# schematic_easyeda.net
KiCad netlist of a schematic drawn in EasyEDA
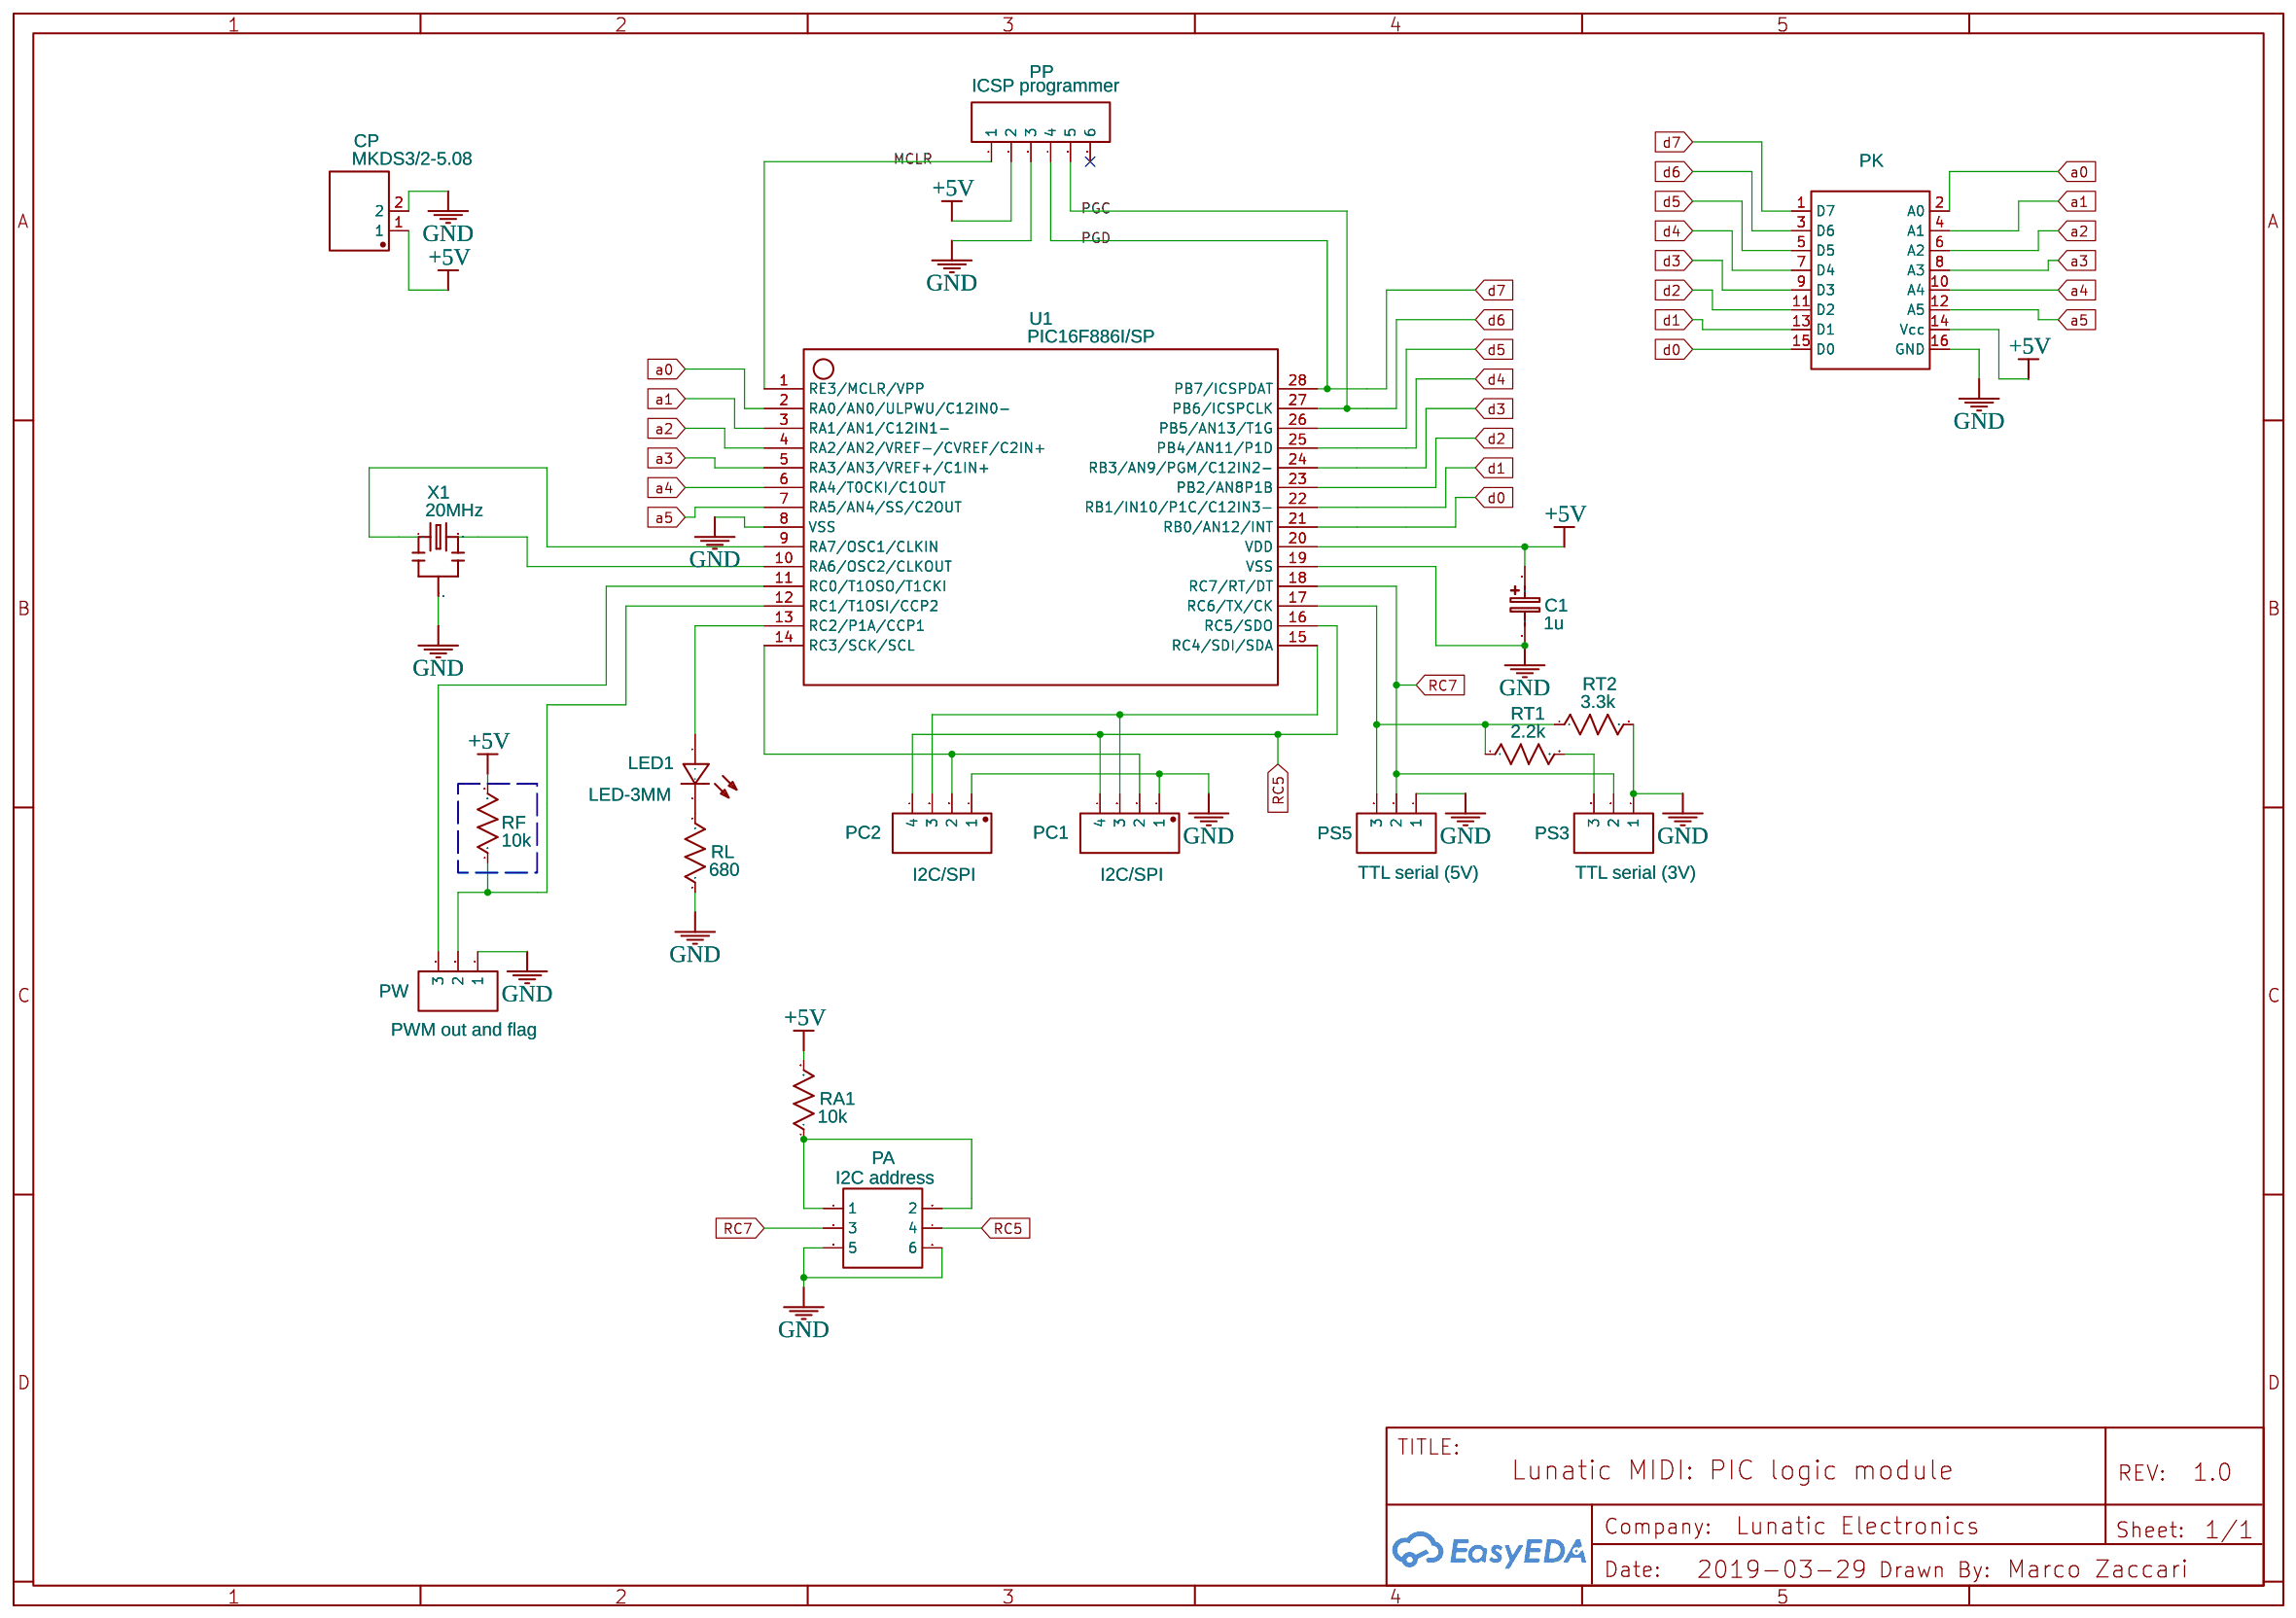
[diagram p0: schematic sheet]

(export (version "E")
  (design (tool "Eeschema 10.0.6"))
  (components
    (comp (ref "C1")
      (value "1u")
      (fields (field (name "BOM_Manufacturer Part") "?"))
      (libsource (lib "") (part "Cap_Electrolytic(TH)_D3.0XF1.5_EU"))
    )
    (comp (ref "CP")
      (value "MKDS3/2-5.08")
      (fields (field (name "BOM_Supplier Part") "C89120"))
      (libsource (lib "") (part "Unknown_180_100"))
    )
    (comp (ref "LED1")
      (value "LED-3MM")
      (fields
        (field (name "BOM_Manufacturer Part") "204-10SURD/S530-A3")
        (field (name "BOM_Supplier Part") "C99772")
      )
      (libsource (lib "") (part "Unknown_345_385"))
    )
    (comp (ref "PA")
      (value "I2C address")
      (fields
        (field (name "BOM_Manufacturer Part") "Header-Male-2.54_2x3")
        (field (name "BOM_Supplier Part") "C65114")
      )
      (libsource (lib "") (part "Unknown_440_615"))
    )
    (comp (ref "PC1")
      (value "I2C/SPI")
      (fields
        (field (name "BOM_Manufacturer Part") "210S-1*4P L=11.6MMGold-plated black")
        (field (name "BOM_Supplier Part") "C124378")
      )
      (libsource (lib "") (part "Unknown_565_410"))
    )
    (comp (ref "PC2")
      (value "I2C/SPI")
      (fields
        (field (name "BOM_Manufacturer Part") "210S-1*4P L=11.6MMGold-plated black")
        (field (name "BOM_Supplier Part") "C124378")
      )
      (libsource (lib "") (part "Unknown_470_410"))
    )
    (comp (ref "PK")
      (value "Lunatic MCU connector")
      (fields (field (name "BOM_Manufacturer Part") "GEM"))
      (libsource (lib "") (part "Unknown_930_130"))
    )
    (comp (ref "PP")
      (value "ICSP programmer")
      (fields
        (field (name "BOM_Manufacturer Part") "Header-Male-2.54_1x6")
        (field (name "BOM_Supplier Part") "C37208")
      )
      (libsource (lib "") (part "Unknown_520_60"))
    )
    (comp (ref "PS3")
      (value "TTL serial (3V)")
      (fields
        (field (name "BOM_Manufacturer Part") "Header2.54mm 1*3P")
        (field (name "BOM_Supplier Part") "C49257")
      )
      (libsource (lib "") (part "Unknown_810_410"))
    )
    (comp (ref "PS5")
      (value "TTL serial (5V)")
      (fields
        (field (name "BOM_Manufacturer Part") "Header2.54mm 1*3P")
        (field (name "BOM_Supplier Part") "C49257")
      )
      (libsource (lib "") (part "Unknown_700_410"))
    )
    (comp (ref "PW")
      (value "PWM out and flag")
      (fields
        (field (name "BOM_Manufacturer Part") "Header2.54mm 1*3P")
        (field (name "BOM_Supplier Part") "C49257")
      )
      (libsource (lib "") (part "Unknown_225_490"))
    )
    (comp (ref "RA1")
      (value "10k")
      (fields (field (name "BOM_Manufacturer Part") "?"))
      (libsource (lib "") (part "Res_AXIAL-0.3(1/8W)_US_3"))
    )
    (comp (ref "RF")
      (value "10k")
      (fields (field (name "BOM_Manufacturer Part") "?"))
      (libsource (lib "") (part "Res_AXIAL-0.3(1/8W)_US"))
    )
    (comp (ref "RL")
      (value "680")
      (fields (field (name "BOM_Manufacturer Part") "?"))
      (libsource (lib "") (part "Res_AXIAL-0.3(1/8W)_US_2"))
    )
    (comp (ref "RT1")
      (value "2.2k")
      (fields (field (name "BOM_Manufacturer Part") "?"))
      (libsource (lib "") (part "Res_AXIAL-0.3(1/8W)_US_1"))
    )
    (comp (ref "RT2")
      (value "3.3k")
      (fields (field (name "BOM_Manufacturer Part") "?"))
      (libsource (lib "") (part "Res_AXIAL-0.3(1/8W)_US_1"))
    )
    (comp (ref "U1")
      (value "PIC16F886I/SP")
      (fields (field (name "BOM_Supplier Part") "C46335"))
      (libsource (lib "") (part "Unknown_510_270"))
    )
    (comp (ref "X1")
      (value "20MHz")
      (fields
        (field (name "BOM_Manufacturer Part") "Resonator 433.92MHZ")
        (field (name "BOM_Supplier Part") "C71016")
      )
      (libsource (lib "") (part "RESONATOR 433.92MHZ"))
    )
  )
  (nets
    (net (code "1") (name "+5V") (class "Default")
      (node (ref "C1") (pin "1") (pinfunction "1_1") (pintype "unspecified"))
      (node (ref "CP") (pin "1") (pinfunction "1_1") (pintype "unspecified"))
      (node (ref "PK") (pin "14") (pinfunction "Vcc_14") (pintype "passive"))
      (node (ref "PP") (pin "2") (pinfunction "2_2") (pintype "input"))
      (node (ref "RA1") (pin "2") (pinfunction "2_2") (pintype "unspecified"))
      (node (ref "RF") (pin "2") (pinfunction "2_2") (pintype "unspecified"))
      (node (ref "U1") (pin "20") (pinfunction "VDD_20") (pintype "unspecified"))
    )
    (net (code "2") (name "/MCLR") (class "Default")
      (node (ref "PP") (pin "1") (pinfunction "1_1") (pintype "input"))
      (node (ref "U1") (pin "1") (pinfunction "RE3/MCLR/VPP_1") (pintype "unspecified"))
    )
    (net (code "3") (name "GND") (class "Default")
      (node (ref "C1") (pin "2") (pinfunction "2_2") (pintype "unspecified"))
      (node (ref "CP") (pin "2") (pinfunction "2_2") (pintype "unspecified"))
      (node (ref "PA") (pin "5") (pinfunction "5_5") (pintype "input"))
      (node (ref "PA") (pin "6") (pinfunction "6_6") (pintype "input"))
      (node (ref "PC1") (pin "1") (pinfunction "1_1") (pintype "unspecified"))
      (node (ref "PC2") (pin "1") (pinfunction "1_1") (pintype "unspecified"))
      (node (ref "PK") (pin "16") (pinfunction "GND_16") (pintype "passive"))
      (node (ref "PP") (pin "3") (pinfunction "3_3") (pintype "input"))
      (node (ref "PS3") (pin "1") (pinfunction "1_1") (pintype "input"))
      (node (ref "PS5") (pin "1") (pinfunction "1_1") (pintype "input"))
      (node (ref "PW") (pin "1") (pinfunction "1_1") (pintype "input"))
      (node (ref "RL") (pin "1") (pinfunction "1_1") (pintype "unspecified"))
      (node (ref "RT2") (pin "2") (pinfunction "2_2") (pintype "unspecified"))
      (node (ref "U1") (pin "19") (pinfunction "VSS_19") (pintype "unspecified"))
      (node (ref "U1") (pin "8") (pinfunction "VSS_8") (pintype "unspecified"))
      (node (ref "X1") (pin "2") (pinfunction "2_2") (pintype "unspecified"))
    )
    (net (code "4") (name "Net-(LED1-+)") (class "Default")
      (node (ref "LED1") (pin "1") (pinfunction "+_1") (pintype "unspecified"))
      (node (ref "U1") (pin "13") (pinfunction "RC2/P1A/CCP1_13") (pintype "unspecified"))
    )
    (net (code "5") (name "Net-(LED1--)") (class "Default")
      (node (ref "LED1") (pin "2") (pinfunction "-_2") (pintype "unspecified"))
      (node (ref "RL") (pin "2") (pinfunction "2_2") (pintype "unspecified"))
    )
    (net (code "6") (name "Net-(PA-Pad1)") (class "Default")
      (node (ref "PA") (pin "1") (pinfunction "1_1") (pintype "input"))
      (node (ref "PA") (pin "2") (pinfunction "2_2") (pintype "input"))
      (node (ref "RA1") (pin "1") (pinfunction "1_1") (pintype "unspecified"))
    )
    (net (code "7") (name "Net-(PS3-Pad3)") (class "Default")
      (node (ref "PS3") (pin "3") (pinfunction "3_3") (pintype "input"))
      (node (ref "RT1") (pin "2") (pinfunction "2_2") (pintype "unspecified"))
    )
    (net (code "8") (name "Net-(U1-RA6{slash}OSC2{slash}CLKOUT)") (class "Default")
      (node (ref "U1") (pin "10") (pinfunction "RA6/OSC2/CLKOUT_10") (pintype "unspecified"))
      (node (ref "X1") (pin "3") (pinfunction "3_3") (pintype "unspecified"))
    )
    (net (code "9") (name "Net-(U1-RA7{slash}OSC1{slash}CLKIN)") (class "Default")
      (node (ref "U1") (pin "9") (pinfunction "RA7/OSC1/CLKIN_9") (pintype "unspecified"))
      (node (ref "X1") (pin "1") (pinfunction "1_1") (pintype "unspecified"))
    )
    (net (code "10") (name "Net-(U1-RC0{slash}T1OSO{slash}T1CKI)") (class "Default")
      (node (ref "PW") (pin "3") (pinfunction "3_3") (pintype "input"))
      (node (ref "U1") (pin "11") (pinfunction "RC0/T1OSO/T1CKI_11") (pintype "unspecified"))
    )
    (net (code "11") (name "Net-(U1-RC1{slash}T1OSI{slash}CCP2)") (class "Default")
      (node (ref "PW") (pin "2") (pinfunction "2_2") (pintype "input"))
      (node (ref "RF") (pin "1") (pinfunction "1_1") (pintype "unspecified"))
      (node (ref "U1") (pin "12") (pinfunction "RC1/T1OSI/CCP2_12") (pintype "unspecified"))
    )
    (net (code "12") (name "Net-(U1-RC3{slash}SCK{slash}SCL)") (class "Default")
      (node (ref "PC1") (pin "2") (pinfunction "2_2") (pintype "unspecified"))
      (node (ref "PC2") (pin "2") (pinfunction "2_2") (pintype "unspecified"))
      (node (ref "U1") (pin "14") (pinfunction "RC3/SCK/SCL_14") (pintype "unspecified"))
    )
    (net (code "13") (name "Net-(U1-RC4{slash}SDI{slash}SDA)") (class "Default")
      (node (ref "PC1") (pin "3") (pinfunction "3_3") (pintype "unspecified"))
      (node (ref "PC2") (pin "3") (pinfunction "3_3") (pintype "unspecified"))
      (node (ref "U1") (pin "15") (pinfunction "RC4/SDI/SDA_15") (pintype "unspecified"))
    )
    (net (code "14") (name "Net-(U1-RC6{slash}TX{slash}CK)") (class "Default")
      (node (ref "PS5") (pin "3") (pinfunction "3_3") (pintype "input"))
      (node (ref "RT1") (pin "1") (pinfunction "1_1") (pintype "unspecified"))
      (node (ref "RT2") (pin "1") (pinfunction "1_1") (pintype "unspecified"))
      (node (ref "U1") (pin "17") (pinfunction "RC6/TX/CK_17") (pintype "unspecified"))
    )
    (net (code "15") (name "RC5") (class "Default")
      (node (ref "PA") (pin "4") (pinfunction "4_4") (pintype "input"))
      (node (ref "PC1") (pin "4") (pinfunction "4_4") (pintype "unspecified"))
      (node (ref "PC2") (pin "4") (pinfunction "4_4") (pintype "unspecified"))
      (node (ref "U1") (pin "16") (pinfunction "RC5/SDO_16") (pintype "unspecified"))
    )
    (net (code "16") (name "RC7") (class "Default")
      (node (ref "PA") (pin "3") (pinfunction "3_3") (pintype "input"))
      (node (ref "PS3") (pin "2") (pinfunction "2_2") (pintype "input"))
      (node (ref "PS5") (pin "2") (pinfunction "2_2") (pintype "input"))
      (node (ref "U1") (pin "18") (pinfunction "RC7/RT/DT_18") (pintype "unspecified"))
    )
    (net (code "17") (name "a0") (class "Default")
      (node (ref "PK") (pin "2") (pinfunction "A0_2") (pintype "output"))
      (node (ref "U1") (pin "2") (pinfunction "RA0/AN0/ULPWU/C12IN0-_2") (pintype "unspecified"))
    )
    (net (code "18") (name "a1") (class "Default")
      (node (ref "PK") (pin "4") (pinfunction "A1_4") (pintype "output"))
      (node (ref "U1") (pin "3") (pinfunction "RA1/AN1/C12IN1-_3") (pintype "unspecified"))
    )
    (net (code "19") (name "a2") (class "Default")
      (node (ref "PK") (pin "6") (pinfunction "A2_6") (pintype "output"))
      (node (ref "U1") (pin "4") (pinfunction "RA2/AN2/VREF-/CVREF/C2IN+_4") (pintype "unspecified"))
    )
    (net (code "20") (name "a3") (class "Default")
      (node (ref "PK") (pin "8") (pinfunction "A3_8") (pintype "output"))
      (node (ref "U1") (pin "5") (pinfunction "RA3/AN3/VREF+/C1IN+_5") (pintype "unspecified"))
    )
    (net (code "21") (name "a4") (class "Default")
      (node (ref "PK") (pin "10") (pinfunction "A4_10") (pintype "output"))
      (node (ref "U1") (pin "6") (pinfunction "RA4/T0CKI/C1OUT_6") (pintype "unspecified"))
    )
    (net (code "22") (name "a5") (class "Default")
      (node (ref "PK") (pin "12") (pinfunction "A5_12") (pintype "output"))
      (node (ref "U1") (pin "7") (pinfunction "RA5/AN4/SS/C2OUT_7") (pintype "unspecified"))
    )
    (net (code "23") (name "d0") (class "Default")
      (node (ref "PK") (pin "15") (pinfunction "D0_15") (pintype "bidirectional"))
      (node (ref "U1") (pin "21") (pinfunction "RB0/AN12/INT_21") (pintype "unspecified"))
    )
    (net (code "24") (name "d1") (class "Default")
      (node (ref "PK") (pin "13") (pinfunction "D1_13") (pintype "bidirectional"))
      (node (ref "U1") (pin "22") (pinfunction "RB1/IN10/P1C/C12IN3-_22") (pintype "unspecified"))
    )
    (net (code "25") (name "d2") (class "Default")
      (node (ref "PK") (pin "11") (pinfunction "D2_11") (pintype "bidirectional"))
      (node (ref "U1") (pin "23") (pinfunction "PB2/AN8P1B_23") (pintype "unspecified"))
    )
    (net (code "26") (name "d3") (class "Default")
      (node (ref "PK") (pin "9") (pinfunction "D3_9") (pintype "bidirectional"))
      (node (ref "U1") (pin "24") (pinfunction "RB3/AN9/PGM/C12IN2-_24") (pintype "unspecified"))
    )
    (net (code "27") (name "d4") (class "Default")
      (node (ref "PK") (pin "7") (pinfunction "D4_7") (pintype "bidirectional"))
      (node (ref "U1") (pin "25") (pinfunction "PB4/AN11/P1D_25") (pintype "unspecified"))
    )
    (net (code "28") (name "d5") (class "Default")
      (node (ref "PK") (pin "5") (pinfunction "D5_5") (pintype "bidirectional"))
      (node (ref "U1") (pin "26") (pinfunction "PB5/AN13/T1G_26") (pintype "unspecified"))
    )
    (net (code "29") (name "d6") (class "Default")
      (node (ref "PK") (pin "3") (pinfunction "D6_3") (pintype "bidirectional"))
      (node (ref "PP") (pin "5") (pinfunction "5_5") (pintype "input"))
      (node (ref "U1") (pin "27") (pinfunction "PB6/ICSPCLK_27") (pintype "unspecified"))
    )
    (net (code "30") (name "d7") (class "Default")
      (node (ref "PK") (pin "1") (pinfunction "D7_1") (pintype "bidirectional"))
      (node (ref "PP") (pin "4") (pinfunction "4_4") (pintype "input"))
      (node (ref "U1") (pin "28") (pinfunction "PB7/ICSPDAT_28") (pintype "unspecified"))
    )
    (net (code "31") (name "unconnected-(PP-Pad6)") (class "Default")
      (node (ref "PP") (pin "6") (pinfunction "6_6") (pintype "input+no_connect"))
    )
  )
)
